# L506_M_V1_1.net
KiCad netlist of a schematic drawn in Altium Designer
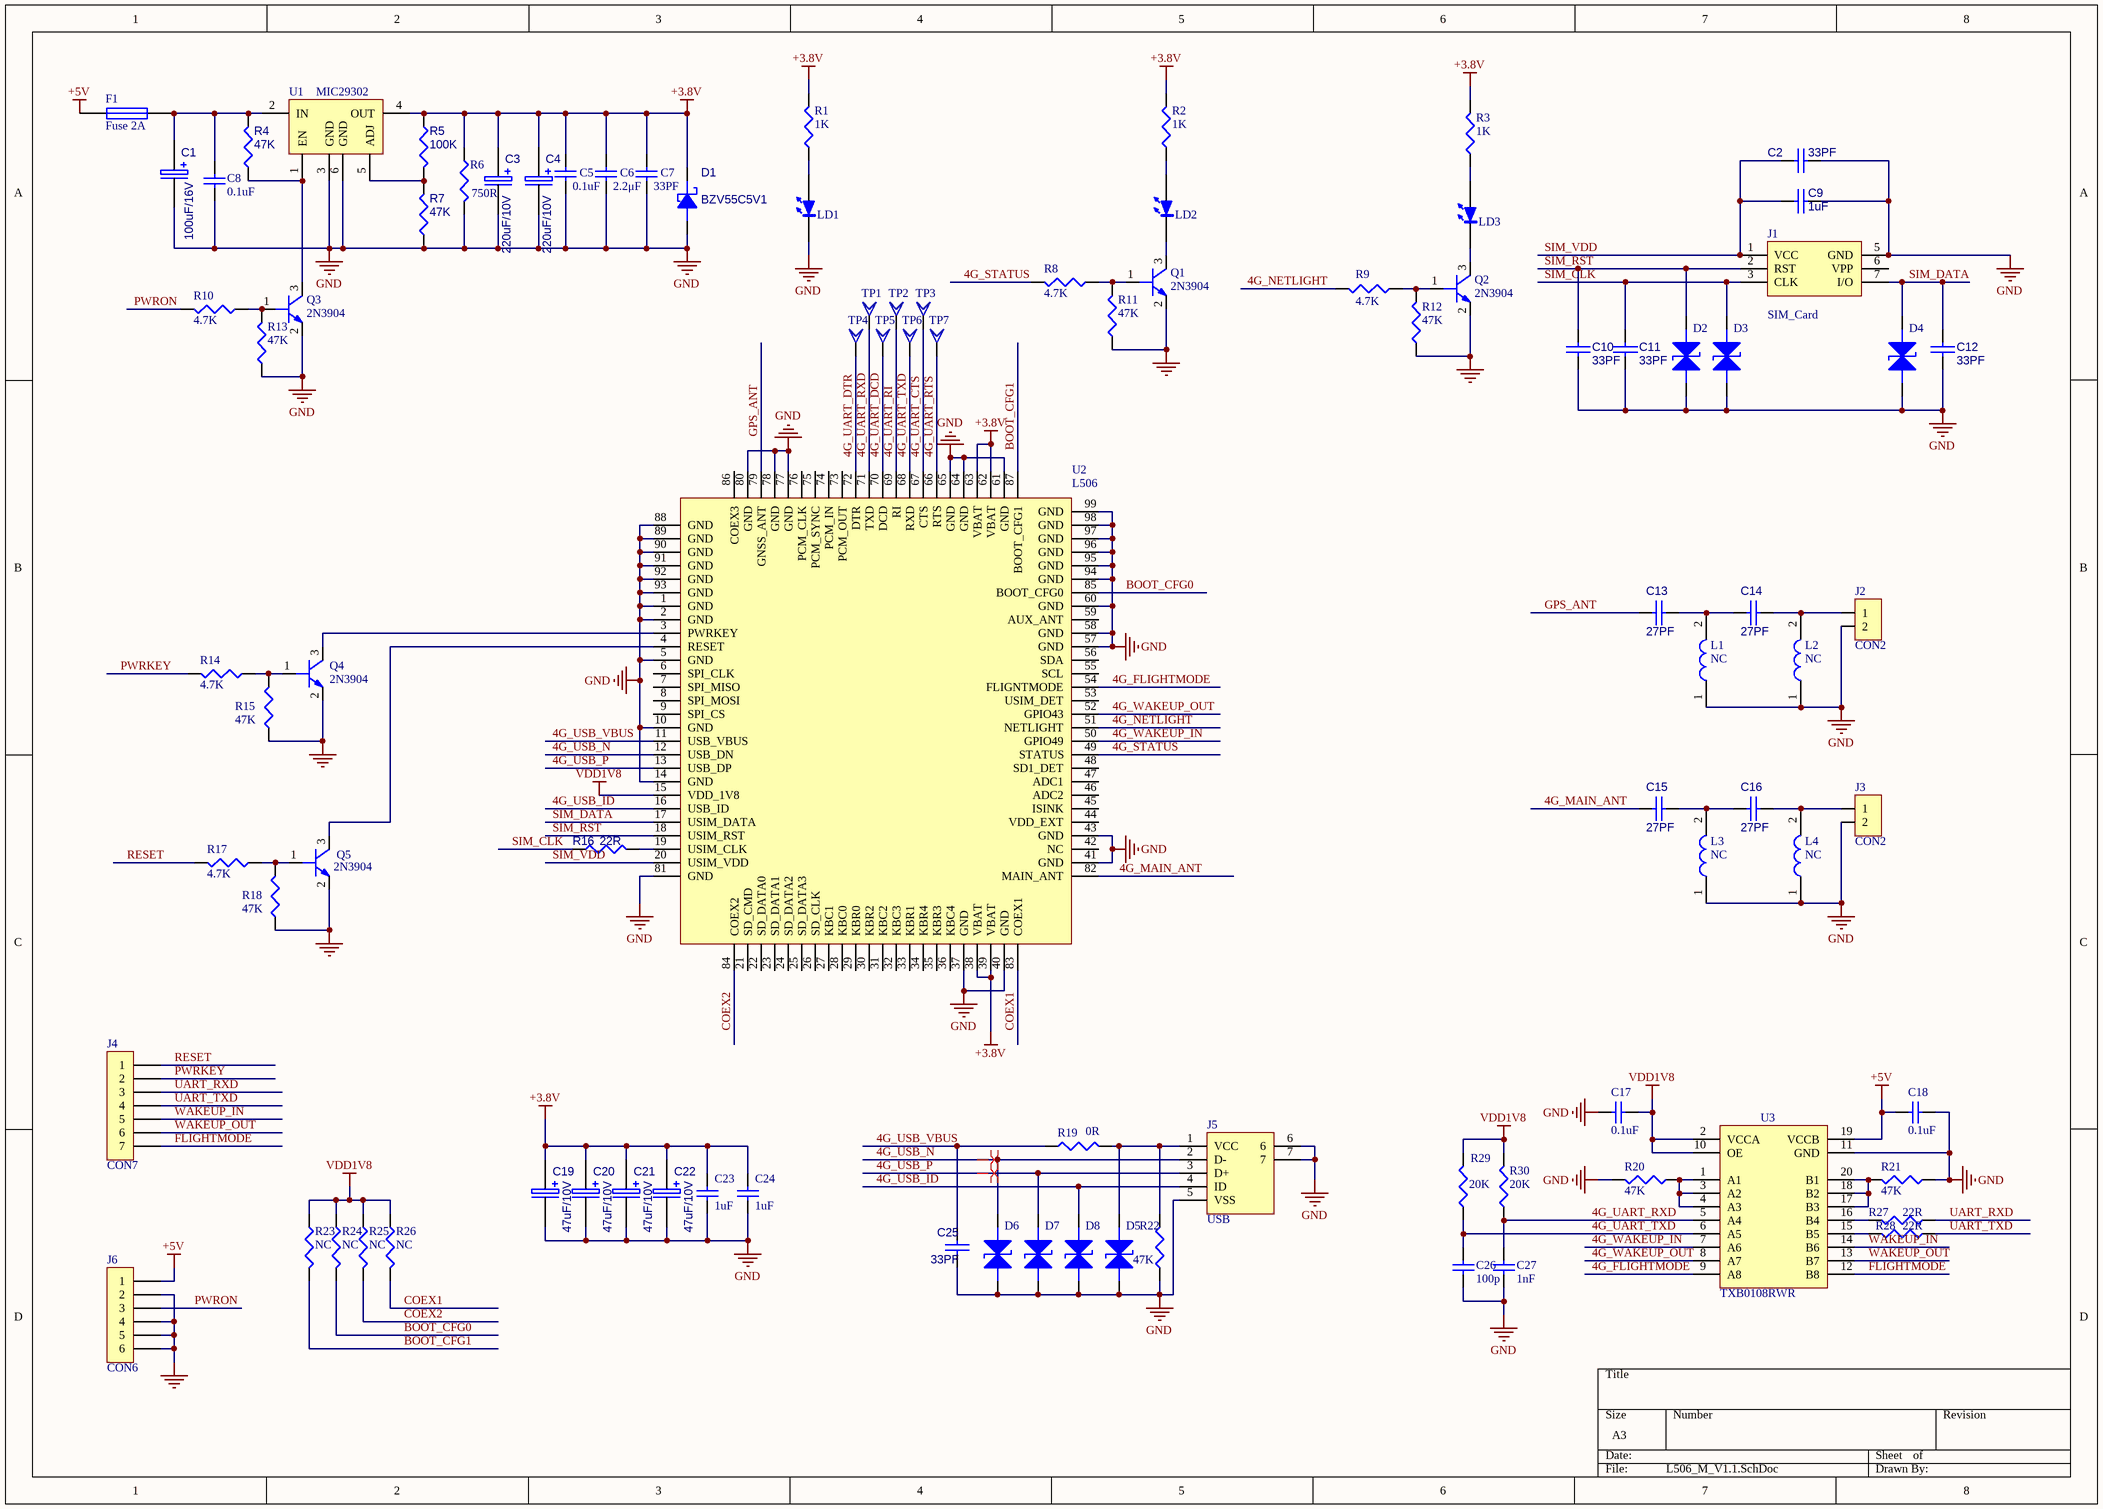
[diagram p0: L506_M_V1.1.SchDoc]

(export (version "E")
  (design (tool "Eeschema 10.0.6"))
  (components
    (comp (ref "C1")
      (value "100uF/16V")
      (footprint "C_TAN_C")
      (description "E-CAP")
      (libsource (lib "*") (part "ECAP"))
    )
    (comp (ref "C2")
      (value "33PF")
      (footprint "0603_C")
      (description "CAP")
      (libsource (lib "") (part "CAP_1"))
    )
    (comp (ref "C3")
      (value "220uF/10V")
      (footprint "C_TAN_D")
      (description "E-CAP")
      (libsource (lib "*") (part "ECAP"))
    )
    (comp (ref "C4")
      (value "220uF/10V")
      (footprint "C_TAN_D")
      (description "E-CAP")
      (libsource (lib "*") (part "ECAP"))
    )
    (comp (ref "C5")
      (value "0.1uF")
      (footprint "0603_C")
      (description "Capacitor")
      (fields (field (name "PUBLISHER") "Altium Limited"))
      (libsource (lib "EP_MCB_V3.00") (part "Cap Semi"))
    )
    (comp (ref "C6")
      (value "2.2μF")
      (footprint "0603_C")
      (description "Capacitor")
      (fields (field (name "PUBLISHER") "Altium Limited"))
      (libsource (lib "EP_MCB_V3.00") (part "Cap Semi"))
    )
    (comp (ref "C7")
      (value "33PF")
      (footprint "0603_C")
      (description "Capacitor")
      (fields (field (name "PUBLISHER") "Altium Limited"))
      (libsource (lib "EP_MCB_V3.00") (part "Cap Semi"))
    )
    (comp (ref "C8")
      (value "0.1uF")
      (footprint "0603_C")
      (description "Capacitor")
      (fields (field (name "PUBLISHER") "Altium Limited"))
      (libsource (lib "EP_MCB_V3.00") (part "Cap Semi"))
    )
    (comp (ref "C9")
      (value "1uF")
      (footprint "0603_C")
      (description "CAP")
      (libsource (lib "") (part "CAP_1"))
    )
    (comp (ref "C10")
      (value "33PF")
      (footprint "0603_C")
      (description "CAP")
      (libsource (lib "*") (part "CAP"))
    )
    (comp (ref "C11")
      (value "33PF")
      (footprint "0603_C")
      (description "CAP")
      (libsource (lib "*") (part "CAP"))
    )
    (comp (ref "C12")
      (value "33PF")
      (footprint "0603_C")
      (description "CAP")
      (libsource (lib "*") (part "CAP"))
    )
    (comp (ref "C13")
      (value "27PF")
      (footprint "0603_C")
      (description "CAP")
      (libsource (lib "") (part "CAP_1"))
    )
    (comp (ref "C14")
      (value "27PF")
      (footprint "0603_C")
      (description "CAP")
      (libsource (lib "") (part "CAP_1"))
    )
    (comp (ref "C15")
      (value "27PF")
      (footprint "0603_C")
      (description "CAP")
      (libsource (lib "") (part "CAP_1"))
    )
    (comp (ref "C16")
      (value "27PF")
      (footprint "0603_C")
      (description "CAP")
      (libsource (lib "") (part "CAP_1"))
    )
    (comp (ref "C17")
      (value "0.1uF")
      (footprint "0603_C")
      (description "Capacitor")
      (fields (field (name "PUBLISHER") "Altium Limited"))
      (libsource (lib "EP_MCB_V3.00") (part "Cap Semi"))
    )
    (comp (ref "C18")
      (value "0.1uF")
      (footprint "0603_C")
      (description "Capacitor")
      (fields (field (name "PUBLISHER") "Altium Limited"))
      (libsource (lib "EP_MCB_V3.00") (part "Cap Semi"))
    )
    (comp (ref "C19")
      (value "47uF/10V")
      (footprint "C_TAN_B")
      (description "E-CAP")
      (libsource (lib "*") (part "ECAP"))
    )
    (comp (ref "C20")
      (value "47uF/10V")
      (footprint "C_TAN_B")
      (description "E-CAP")
      (libsource (lib "*") (part "ECAP"))
    )
    (comp (ref "C21")
      (value "47uF/10V")
      (footprint "C_TAN_B")
      (description "E-CAP")
      (libsource (lib "*") (part "ECAP"))
    )
    (comp (ref "C22")
      (value "47uF/10V")
      (footprint "C_TAN_B")
      (description "E-CAP")
      (libsource (lib "*") (part "ECAP"))
    )
    (comp (ref "C23")
      (value "1uF")
      (footprint "0603_C")
      (description "Capacitor")
      (fields (field (name "PUBLISHER") "Altium Limited"))
      (libsource (lib "EP_MCB_V3.00") (part "Cap Semi"))
    )
    (comp (ref "C24")
      (value "1uF")
      (footprint "0603_C")
      (description "Capacitor")
      (fields (field (name "PUBLISHER") "Altium Limited"))
      (libsource (lib "EP_MCB_V3.00") (part "Cap Semi"))
    )
    (comp (ref "C25")
      (value "33PF")
      (footprint "0603_C")
      (description "CAP")
      (libsource (lib "*") (part "CAP"))
    )
    (comp (ref "C26")
      (value "100p")
      (footprint "0603_C")
      (description "Capacitor")
      (fields (field (name "PUBLISHER") "Altium Limited"))
      (libsource (lib "EP_MCB_V3.00") (part "Cap Semi"))
    )
    (comp (ref "C27")
      (value "1nF")
      (footprint "0603_C")
      (description "Capacitor")
      (fields (field (name "PUBLISHER") "Altium Limited"))
      (libsource (lib "EP_MCB_V3.00") (part "Cap Semi"))
    )
    (comp (ref "D1")
      (value "BZV55C5V1")
      (footprint "SOD-80")
      (libsource (lib "EP_MCB_V4.1") (part "DIODE SCHOTTKY"))
    )
    (comp (ref "D2")
      (value "EGA10603V05A1-B")
      (footprint "0603_R")
      (libsource (lib "MySchlib") (part "DIODE TVS BI-DIR"))
    )
    (comp (ref "D3")
      (value "EGA10603V05A1-B")
      (footprint "0603_R")
      (libsource (lib "MySchlib") (part "DIODE TVS BI-DIR"))
    )
    (comp (ref "D4")
      (value "EGA10603V05A1-B")
      (footprint "0603_R")
      (libsource (lib "MySchlib") (part "DIODE TVS BI-DIR"))
    )
    (comp (ref "D5")
      (value "EGA10603V05A1-B")
      (footprint "0603_R")
      (libsource (lib "MySchlib") (part "DIODE TVS BI-DIR"))
    )
    (comp (ref "D6")
      (value "EGA10603V05A1-B")
      (footprint "0603_R")
      (libsource (lib "MySchlib") (part "DIODE TVS BI-DIR"))
    )
    (comp (ref "D7")
      (value "EGA10603V05A1-B")
      (footprint "0603_R")
      (libsource (lib "MySchlib") (part "DIODE TVS BI-DIR"))
    )
    (comp (ref "D8")
      (value "EGA10603V05A1-B")
      (footprint "0603_R")
      (libsource (lib "MySchlib") (part "DIODE TVS BI-DIR"))
    )
    (comp (ref "F1")
      (value "Fuse 2A")
      (footprint "1812_F")
      (description "Fuse")
      (fields (field (name "PUBLISHER") "Altium Limited"))
      (libsource (lib "Miscellaneous Devices") (part "Fuse 1"))
    )
    (comp (ref "J1")
      (value "SIM_Card")
      (footprint "MicroSIM-6")
      (libsource (lib "MySchlib") (part "SIM_Card"))
    )
    (comp (ref "J2") (value "CON2") (footprint "RF-Z") (libsource (lib "MySchlib") (part "CON2")))
    (comp (ref "J3") (value "CON2") (footprint "RF-Z") (libsource (lib "MySchlib") (part "CON2")))
    (comp (ref "J4") (value "CON7") (footprint "SIP7") (libsource (lib "MySchlib") (part "CON7")))
    (comp (ref "J5") (value "USB") (libsource (lib "MySchlib") (part "USB-M")))
    (comp (ref "J6") (value "CON6") (footprint "SIP6") (libsource (lib "MySchlib") (part "CON6")))
    (comp (ref "L1") (value "NC") (footprint "0603_R") (libsource (lib "MySchlib") (part "L")))
    (comp (ref "L2") (value "NC") (footprint "0603_R") (libsource (lib "MySchlib") (part "L")))
    (comp (ref "L3") (value "NC") (footprint "0603_R") (libsource (lib "MySchlib") (part "L")))
    (comp (ref "L4") (value "NC") (footprint "0603_R") (libsource (lib "MySchlib") (part "L")))
    (comp (ref "LD1")
      (value "WHITE")
      (footprint "LED_0603")
      (description "LED")
      (libsource (lib "*") (part "LED"))
    )
    (comp (ref "LD2")
      (value "WHITE")
      (footprint "LED_0603")
      (description "LED")
      (libsource (lib "*") (part "LED"))
    )
    (comp (ref "LD3")
      (value "WHITE")
      (footprint "LED_0603")
      (description "LED")
      (libsource (lib "*") (part "LED"))
    )
    (comp (ref "Q1") (value "2N3904") (footprint "SOT23") (libsource (lib "MySchlib") (part "NPN")))
    (comp (ref "Q2") (value "2N3904") (footprint "SOT23") (libsource (lib "MySchlib") (part "NPN")))
    (comp (ref "Q3") (value "2N3904") (footprint "SOT23") (libsource (lib "MySchlib") (part "NPN")))
    (comp (ref "Q4") (value "2N3904") (footprint "SOT23") (libsource (lib "MySchlib") (part "NPN")))
    (comp (ref "Q5") (value "2N3904") (footprint "SOT23") (libsource (lib "MySchlib") (part "NPN")))
    (comp (ref "R1") (value "1K") (footprint "0603_R") (libsource (lib "MySchlib") (part "RES1")))
    (comp (ref "R2") (value "1K") (footprint "0603_R") (libsource (lib "MySchlib") (part "RES1")))
    (comp (ref "R3") (value "1K") (footprint "0603_R") (libsource (lib "MySchlib") (part "RES1")))
    (comp (ref "R4")
      (value "47K")
      (footprint "0603_R")
      (description "RESISTOR")
      (libsource (lib "*") (part "R0.25W"))
    )
    (comp (ref "R5")
      (value "100K")
      (footprint "0603_R")
      (description "RESISTOR")
      (libsource (lib "*") (part "R0.25W"))
    )
    (comp (ref "R6") (value "750R") (footprint "0603_R") (libsource (lib "") (part "RES1_1")))
    (comp (ref "R7")
      (value "47K")
      (footprint "0603_R")
      (description "RESISTOR")
      (libsource (lib "*") (part "R0.25W"))
    )
    (comp (ref "R8") (value "4.7K") (footprint "0603_R") (libsource (lib "MySchlib") (part "RES1")))
    (comp (ref "R9") (value "4.7K") (footprint "0603_R") (libsource (lib "MySchlib") (part "RES1")))
    (comp (ref "R10") (value "4.7K") (footprint "0603_R") (libsource (lib "MySchlib") (part "RES1")))
    (comp (ref "R11") (value "47K") (footprint "0603_R") (libsource (lib "MySchlib") (part "RES1")))
    (comp (ref "R12") (value "47K") (footprint "0603_R") (libsource (lib "MySchlib") (part "RES1")))
    (comp (ref "R13") (value "47K") (footprint "0603_R") (libsource (lib "MySchlib") (part "RES1")))
    (comp (ref "R14") (value "4.7K") (footprint "0603_R") (libsource (lib "MySchlib") (part "RES1")))
    (comp (ref "R15") (value "47K") (footprint "0603_R") (libsource (lib "MySchlib") (part "RES1")))
    (comp (ref "R16")
      (value "22R")
      (footprint "0603_R")
      (description "RESISTOR")
      (libsource (lib "*") (part "R0.25W"))
    )
    (comp (ref "R17") (value "4.7K") (footprint "0603_R") (libsource (lib "MySchlib") (part "RES1")))
    (comp (ref "R18") (value "47K") (footprint "0603_R") (libsource (lib "MySchlib") (part "RES1")))
    (comp (ref "R19") (value "0R") (footprint "0603_R") (libsource (lib "MySchlib") (part "RES1")))
    (comp (ref "R20") (value "47K") (footprint "0603_R") (libsource (lib "MySchlib") (part "RES1")))
    (comp (ref "R21") (value "47K") (footprint "0603_R") (libsource (lib "MySchlib") (part "RES1")))
    (comp (ref "R22") (value "47K") (footprint "0603_R") (libsource (lib "MySchlib") (part "RES1")))
    (comp (ref "R23") (value "NC") (footprint "0603_R") (libsource (lib "MySchlib") (part "RES1")))
    (comp (ref "R24") (value "NC") (footprint "0603_R") (libsource (lib "MySchlib") (part "RES1")))
    (comp (ref "R25") (value "NC") (footprint "0603_R") (libsource (lib "MySchlib") (part "RES1")))
    (comp (ref "R26") (value "NC") (footprint "0603_R") (libsource (lib "MySchlib") (part "RES1")))
    (comp (ref "R27") (value "22R") (footprint "0603_R") (libsource (lib "MySchlib") (part "RES1")))
    (comp (ref "R28") (value "22R") (footprint "0603_R") (libsource (lib "MySchlib") (part "RES1")))
    (comp (ref "R29") (value "20K") (footprint "0603_R") (libsource (lib "MySchlib") (part "RES1")))
    (comp (ref "R30") (value "20K") (footprint "0603_R") (libsource (lib "MySchlib") (part "RES1")))
    (comp (ref "TP1")
      (value "Component_1")
      (footprint "TP-40")
      (libsource (lib "MySchlib") (part "Component_1"))
    )
    (comp (ref "TP2")
      (value "Component_1")
      (footprint "TP-40")
      (libsource (lib "MySchlib") (part "Component_1"))
    )
    (comp (ref "TP3")
      (value "Component_1")
      (footprint "TP-40")
      (libsource (lib "MySchlib") (part "Component_1"))
    )
    (comp (ref "TP4")
      (value "Component_1")
      (footprint "TP-40")
      (libsource (lib "MySchlib") (part "Component_1"))
    )
    (comp (ref "TP5")
      (value "Component_1")
      (footprint "TP-40")
      (libsource (lib "MySchlib") (part "Component_1"))
    )
    (comp (ref "TP6")
      (value "Component_1")
      (footprint "TP-40")
      (libsource (lib "MySchlib") (part "Component_1"))
    )
    (comp (ref "TP7")
      (value "Component_1")
      (footprint "TP-40")
      (libsource (lib "MySchlib") (part "Component_1"))
    )
    (comp (ref "U1") (value "MIC29302") (footprint "TO-263-5") (libsource (lib "MySchlib") (part "MIC29302")))
    (comp (ref "U2") (value "L506") (footprint "L506") (libsource (lib "MySchlib") (part "L506")))
    (comp (ref "U3")
      (value "TXB0108RWR")
      (footprint "TSSP20")
      (libsource (lib "MySchlib") (part "TXB0108RGYR"))
    )
  )
  (nets
    (net (code "1") (name "+3.8V") (class "Default")
      (node (ref "C19") (pin "1") (pinfunction "+_1") (pintype "passive"))
      (node (ref "C20") (pin "1") (pinfunction "+_1") (pintype "passive"))
      (node (ref "C21") (pin "1") (pinfunction "+_1") (pintype "passive"))
      (node (ref "C22") (pin "1") (pinfunction "+_1") (pintype "passive"))
      (node (ref "C23") (pin "2") (pinfunction "2_2") (pintype "passive"))
      (node (ref "C24") (pin "2") (pinfunction "2_2") (pintype "passive"))
      (node (ref "C3") (pin "1") (pinfunction "+_1") (pintype "passive"))
      (node (ref "C4") (pin "1") (pinfunction "+_1") (pintype "passive"))
      (node (ref "C5") (pin "2") (pinfunction "2_2") (pintype "passive"))
      (node (ref "C6") (pin "2") (pinfunction "2_2") (pintype "passive"))
      (node (ref "C7") (pin "2") (pinfunction "2_2") (pintype "passive"))
      (node (ref "D1") (pin "2") (pinfunction "CATHODE_2") (pintype "passive"))
      (node (ref "R1") (pin "1") (pinfunction "1_1") (pintype "passive"))
      (node (ref "R2") (pin "1") (pinfunction "1_1") (pintype "passive"))
      (node (ref "R3") (pin "1") (pinfunction "1_1") (pintype "passive"))
      (node (ref "R5") (pin "2") (pinfunction "2_2") (pintype "passive"))
      (node (ref "R6") (pin "2") (pinfunction "2_2") (pintype "passive"))
      (node (ref "U1") (pin "4") (pinfunction "OUT_4") (pintype "passive"))
      (node (ref "U2") (pin "38") (pinfunction "VBAT_38") (pintype "passive"))
      (node (ref "U2") (pin "39") (pinfunction "VBAT_39") (pintype "passive"))
      (node (ref "U2") (pin "62") (pinfunction "VBAT_62") (pintype "passive"))
      (node (ref "U2") (pin "63") (pinfunction "VBAT_63") (pintype "passive"))
    )
    (net (code "2") (name "+5V") (class "Default")
      (node (ref "C18") (pin "2") (pinfunction "2_2") (pintype "passive"))
      (node (ref "F1") (pin "1") (pinfunction "1_1") (pintype "passive"))
      (node (ref "J6") (pin "1") (pinfunction "1_1") (pintype "passive"))
      (node (ref "U3") (pin "19") (pinfunction "VCCB_19") (pintype "passive"))
    )
    (net (code "3") (name "/4G_FLIGHTMODE") (class "Default")
      (node (ref "U2") (pin "54") (pinfunction "FLIGNTMODE_54") (pintype "passive"))
      (node (ref "U3") (pin "9") (pinfunction "A8_9") (pintype "passive"))
    )
    (net (code "4") (name "/4G_MAIN_ANT") (class "Default")
      (node (ref "C15") (pin "1") (pinfunction "1_1") (pintype "passive"))
      (node (ref "U2") (pin "82") (pinfunction "MAIN_ANT_82") (pintype "passive"))
    )
    (net (code "5") (name "/4G_NETLIGHT") (class "Default")
      (node (ref "R9") (pin "1") (pinfunction "1_1") (pintype "passive"))
      (node (ref "U2") (pin "51") (pinfunction "NETLIGHT_51") (pintype "passive"))
    )
    (net (code "6") (name "/4G_STATUS") (class "Default")
      (node (ref "R8") (pin "1") (pinfunction "1_1") (pintype "passive"))
      (node (ref "U2") (pin "49") (pinfunction "STATUS_49") (pintype "passive"))
    )
    (net (code "7") (name "/4G_UART_CTS") (class "Default")
      (node (ref "TP3") (pin "1") (pinfunction "1_1") (pintype "passive"))
      (node (ref "U2") (pin "67") (pinfunction "CTS_67") (pintype "passive"))
    )
    (net (code "8") (name "/4G_UART_DCD") (class "Default")
      (node (ref "TP5") (pin "1") (pinfunction "1_1") (pintype "passive"))
      (node (ref "U2") (pin "70") (pinfunction "DCD_70") (pintype "passive"))
    )
    (net (code "9") (name "/4G_UART_DTR") (class "Default")
      (node (ref "TP4") (pin "1") (pinfunction "1_1") (pintype "passive"))
      (node (ref "U2") (pin "72") (pinfunction "DTR_72") (pintype "passive"))
    )
    (net (code "10") (name "/4G_UART_RI") (class "Default")
      (node (ref "TP2") (pin "1") (pinfunction "1_1") (pintype "passive"))
      (node (ref "U2") (pin "69") (pinfunction "RI_69") (pintype "passive"))
    )
    (net (code "11") (name "/4G_UART_RTS") (class "Default")
      (node (ref "TP7") (pin "1") (pinfunction "1_1") (pintype "passive"))
      (node (ref "U2") (pin "66") (pinfunction "RTS_66") (pintype "passive"))
    )
    (net (code "12") (name "/4G_UART_RXD") (class "Default")
      (node (ref "C27") (pin "2") (pinfunction "2_2") (pintype "passive"))
      (node (ref "R30") (pin "1") (pinfunction "1_1") (pintype "passive"))
      (node (ref "TP1") (pin "1") (pinfunction "1_1") (pintype "passive"))
      (node (ref "U2") (pin "71") (pinfunction "TXD_71") (pintype "passive"))
      (node (ref "U3") (pin "5") (pinfunction "A4_5") (pintype "passive"))
    )
    (net (code "13") (name "/4G_UART_TXD") (class "Default")
      (node (ref "C26") (pin "2") (pinfunction "2_2") (pintype "passive"))
      (node (ref "R29") (pin "1") (pinfunction "1_1") (pintype "passive"))
      (node (ref "TP6") (pin "1") (pinfunction "1_1") (pintype "passive"))
      (node (ref "U2") (pin "68") (pinfunction "RXD_68") (pintype "passive"))
      (node (ref "U3") (pin "6") (pinfunction "A5_6") (pintype "passive"))
    )
    (net (code "14") (name "/4G_USB_ID") (class "Default")
      (node (ref "D8") (pin "2") (pinfunction "2_2") (pintype "passive"))
      (node (ref "J5") (pin "4") (pinfunction "ID_4") (pintype "passive"))
      (node (ref "U2") (pin "16") (pinfunction "USB_ID_16") (pintype "passive"))
    )
    (net (code "15") (name "/4G_USB_N") (class "Default")
      (node (ref "D6") (pin "2") (pinfunction "2_2") (pintype "passive"))
      (node (ref "J5") (pin "2") (pinfunction "D-_2") (pintype "passive"))
      (node (ref "U2") (pin "12") (pinfunction "USB_DN_12") (pintype "passive"))
    )
    (net (code "16") (name "/4G_USB_P") (class "Default")
      (node (ref "D7") (pin "2") (pinfunction "2_2") (pintype "passive"))
      (node (ref "J5") (pin "3") (pinfunction "D+_3") (pintype "passive"))
      (node (ref "U2") (pin "13") (pinfunction "USB_DP_13") (pintype "passive"))
    )
    (net (code "17") (name "/4G_USB_VBUS") (class "Default")
      (node (ref "C25") (pin "2") (pinfunction "2_2") (pintype "passive"))
      (node (ref "R19") (pin "1") (pinfunction "1_1") (pintype "passive"))
      (node (ref "U2") (pin "11") (pinfunction "USB_VBUS_11") (pintype "passive"))
    )
    (net (code "18") (name "/4G_WAKEUP_IN") (class "Default")
      (node (ref "U2") (pin "50") (pinfunction "GPIO49_50") (pintype "passive"))
      (node (ref "U3") (pin "7") (pinfunction "A6_7") (pintype "passive"))
    )
    (net (code "19") (name "/4G_WAKEUP_OUT") (class "Default")
      (node (ref "U2") (pin "52") (pinfunction "GPIO43_52") (pintype "passive"))
      (node (ref "U3") (pin "8") (pinfunction "A7_8") (pintype "passive"))
    )
    (net (code "20") (name "/BOOT_CFG0") (class "Default")
      (node (ref "R24") (pin "2") (pinfunction "2_2") (pintype "passive"))
      (node (ref "U2") (pin "85") (pinfunction "BOOT_CFG0_85") (pintype "passive"))
    )
    (net (code "21") (name "/BOOT_CFG1") (class "Default")
      (node (ref "R23") (pin "2") (pinfunction "2_2") (pintype "passive"))
      (node (ref "U2") (pin "87") (pinfunction "BOOT_CFG1_87") (pintype "passive"))
    )
    (net (code "22") (name "/COEX1") (class "Default")
      (node (ref "R26") (pin "2") (pinfunction "2_2") (pintype "passive"))
      (node (ref "U2") (pin "83") (pinfunction "COEX1_83") (pintype "passive"))
    )
    (net (code "23") (name "/COEX2") (class "Default")
      (node (ref "R25") (pin "2") (pinfunction "2_2") (pintype "passive"))
      (node (ref "U2") (pin "84") (pinfunction "COEX2_84") (pintype "passive"))
    )
    (net (code "24") (name "/FLIGHTMODE") (class "Default")
      (node (ref "J4") (pin "7") (pinfunction "7_7") (pintype "passive"))
      (node (ref "U3") (pin "12") (pinfunction "B8_12") (pintype "passive"))
    )
    (net (code "25") (name "/GPS_ANT") (class "Default")
      (node (ref "C13") (pin "1") (pinfunction "1_1") (pintype "passive"))
      (node (ref "U2") (pin "79") (pinfunction "GNSS_ANT_79") (pintype "passive"))
    )
    (net (code "26") (name "/PWRKEY") (class "Default")
      (node (ref "J4") (pin "2") (pinfunction "2_2") (pintype "passive"))
      (node (ref "R14") (pin "1") (pinfunction "1_1") (pintype "passive"))
    )
    (net (code "27") (name "/PWRON") (class "Default")
      (node (ref "J6") (pin "3") (pinfunction "3_3") (pintype "passive"))
      (node (ref "R10") (pin "1") (pinfunction "1_1") (pintype "passive"))
    )
    (net (code "28") (name "/RESET") (class "Default")
      (node (ref "J4") (pin "1") (pinfunction "1_1") (pintype "passive"))
      (node (ref "R17") (pin "1") (pinfunction "1_1") (pintype "passive"))
    )
    (net (code "29") (name "/SIM_CLK") (class "Default")
      (node (ref "C11") (pin "2") (pinfunction "2_2") (pintype "passive"))
      (node (ref "D3") (pin "2") (pinfunction "2_2") (pintype "passive"))
      (node (ref "J1") (pin "3") (pinfunction "CLK_3") (pintype "passive"))
      (node (ref "R16") (pin "1") (pinfunction "1_1") (pintype "passive"))
    )
    (net (code "30") (name "/SIM_DATA") (class "Default")
      (node (ref "C12") (pin "2") (pinfunction "2_2") (pintype "passive"))
      (node (ref "D4") (pin "2") (pinfunction "2_2") (pintype "passive"))
      (node (ref "J1") (pin "7") (pinfunction "I/O_7") (pintype "passive"))
      (node (ref "U2") (pin "17") (pinfunction "USIM_DATA_17") (pintype "passive"))
    )
    (net (code "31") (name "/SIM_RST") (class "Default")
      (node (ref "C10") (pin "2") (pinfunction "2_2") (pintype "passive"))
      (node (ref "D2") (pin "2") (pinfunction "2_2") (pintype "passive"))
      (node (ref "J1") (pin "2") (pinfunction "RST_2") (pintype "passive"))
      (node (ref "U2") (pin "18") (pinfunction "USIM_RST_18") (pintype "passive"))
    )
    (net (code "32") (name "/SIM_VDD") (class "Default")
      (node (ref "C2") (pin "1") (pinfunction "1_1") (pintype "passive"))
      (node (ref "C9") (pin "1") (pinfunction "1_1") (pintype "passive"))
      (node (ref "J1") (pin "1") (pinfunction "VCC_1") (pintype "passive"))
      (node (ref "U2") (pin "20") (pinfunction "USIM_VDD_20") (pintype "passive"))
    )
    (net (code "33") (name "/UART_RXD") (class "Default")
      (node (ref "J4") (pin "3") (pinfunction "3_3") (pintype "passive"))
      (node (ref "R27") (pin "1") (pinfunction "1_1") (pintype "passive"))
    )
    (net (code "34") (name "/UART_TXD") (class "Default")
      (node (ref "J4") (pin "4") (pinfunction "4_4") (pintype "passive"))
      (node (ref "R28") (pin "1") (pinfunction "1_1") (pintype "passive"))
    )
    (net (code "35") (name "/WAKEUP_IN") (class "Default")
      (node (ref "J4") (pin "5") (pinfunction "5_5") (pintype "passive"))
      (node (ref "U3") (pin "14") (pinfunction "B6_14") (pintype "passive"))
    )
    (net (code "36") (name "/WAKEUP_OUT") (class "Default")
      (node (ref "J4") (pin "6") (pinfunction "6_6") (pintype "passive"))
      (node (ref "U3") (pin "13") (pinfunction "B7_13") (pintype "passive"))
    )
    (net (code "37") (name "GND") (class "Default")
      (node (ref "C1") (pin "2") (pinfunction "-_2") (pintype "passive"))
      (node (ref "C10") (pin "1") (pinfunction "1_1") (pintype "passive"))
      (node (ref "C11") (pin "1") (pinfunction "1_1") (pintype "passive"))
      (node (ref "C12") (pin "1") (pinfunction "1_1") (pintype "passive"))
      (node (ref "C17") (pin "1") (pinfunction "1_1") (pintype "passive"))
      (node (ref "C18") (pin "1") (pinfunction "1_1") (pintype "passive"))
      (node (ref "C19") (pin "2") (pinfunction "-_2") (pintype "passive"))
      (node (ref "C2") (pin "2") (pinfunction "2_2") (pintype "passive"))
      (node (ref "C20") (pin "2") (pinfunction "-_2") (pintype "passive"))
      (node (ref "C21") (pin "2") (pinfunction "-_2") (pintype "passive"))
      (node (ref "C22") (pin "2") (pinfunction "-_2") (pintype "passive"))
      (node (ref "C23") (pin "1") (pinfunction "1_1") (pintype "passive"))
      (node (ref "C24") (pin "1") (pinfunction "1_1") (pintype "passive"))
      (node (ref "C25") (pin "1") (pinfunction "1_1") (pintype "passive"))
      (node (ref "C26") (pin "1") (pinfunction "1_1") (pintype "passive"))
      (node (ref "C27") (pin "1") (pinfunction "1_1") (pintype "passive"))
      (node (ref "C3") (pin "2") (pinfunction "-_2") (pintype "passive"))
      (node (ref "C4") (pin "2") (pinfunction "-_2") (pintype "passive"))
      (node (ref "C5") (pin "1") (pinfunction "1_1") (pintype "passive"))
      (node (ref "C6") (pin "1") (pinfunction "1_1") (pintype "passive"))
      (node (ref "C7") (pin "1") (pinfunction "1_1") (pintype "passive"))
      (node (ref "C8") (pin "1") (pinfunction "1_1") (pintype "passive"))
      (node (ref "C9") (pin "2") (pinfunction "2_2") (pintype "passive"))
      (node (ref "D1") (pin "1") (pinfunction "ANODE_1") (pintype "passive"))
      (node (ref "D2") (pin "1") (pinfunction "1_1") (pintype "passive"))
      (node (ref "D3") (pin "1") (pinfunction "1_1") (pintype "passive"))
      (node (ref "D4") (pin "1") (pinfunction "1_1") (pintype "passive"))
      (node (ref "D5") (pin "1") (pinfunction "1_1") (pintype "passive"))
      (node (ref "D6") (pin "1") (pinfunction "1_1") (pintype "passive"))
      (node (ref "D7") (pin "1") (pinfunction "1_1") (pintype "passive"))
      (node (ref "D8") (pin "1") (pinfunction "1_1") (pintype "passive"))
      (node (ref "J1") (pin "5") (pinfunction "GND_5") (pintype "passive"))
      (node (ref "J2") (pin "2") (pinfunction "2_2") (pintype "passive"))
      (node (ref "J3") (pin "2") (pinfunction "2_2") (pintype "passive"))
      (node (ref "J5") (pin "5") (pinfunction "VSS_5") (pintype "passive"))
      (node (ref "J5") (pin "6") (pinfunction "6_6") (pintype "passive"))
      (node (ref "J5") (pin "7") (pinfunction "7_7") (pintype "passive"))
      (node (ref "J6") (pin "2") (pinfunction "2_2") (pintype "passive"))
      (node (ref "J6") (pin "4") (pinfunction "4_4") (pintype "passive"))
      (node (ref "J6") (pin "5") (pinfunction "5_5") (pintype "passive"))
      (node (ref "J6") (pin "6") (pinfunction "6_6") (pintype "passive"))
      (node (ref "L1") (pin "1") (pinfunction "1_1") (pintype "passive"))
      (node (ref "L2") (pin "1") (pinfunction "1_1") (pintype "passive"))
      (node (ref "L3") (pin "1") (pinfunction "1_1") (pintype "passive"))
      (node (ref "L4") (pin "1") (pinfunction "1_1") (pintype "passive"))
      (node (ref "LD1") (pin "K") (pinfunction "K_K") (pintype "passive"))
      (node (ref "Q1") (pin "2") (pinfunction "EMITTER_2") (pintype "passive"))
      (node (ref "Q2") (pin "2") (pinfunction "EMITTER_2") (pintype "passive"))
      (node (ref "Q3") (pin "2") (pinfunction "EMITTER_2") (pintype "passive"))
      (node (ref "Q4") (pin "2") (pinfunction "EMITTER_2") (pintype "passive"))
      (node (ref "Q5") (pin "2") (pinfunction "EMITTER_2") (pintype "passive"))
      (node (ref "R11") (pin "2") (pinfunction "2_2") (pintype "passive"))
      (node (ref "R12") (pin "2") (pinfunction "2_2") (pintype "passive"))
      (node (ref "R13") (pin "2") (pinfunction "2_2") (pintype "passive"))
      (node (ref "R15") (pin "2") (pinfunction "2_2") (pintype "passive"))
      (node (ref "R18") (pin "2") (pinfunction "2_2") (pintype "passive"))
      (node (ref "R20") (pin "2") (pinfunction "2_2") (pintype "passive"))
      (node (ref "R21") (pin "1") (pinfunction "1_1") (pintype "passive"))
      (node (ref "R22") (pin "2") (pinfunction "2_2") (pintype "passive"))
      (node (ref "R6") (pin "1") (pinfunction "1_1") (pintype "passive"))
      (node (ref "R7") (pin "2") (pinfunction "2_2") (pintype "passive"))
      (node (ref "U1") (pin "3") (pinfunction "GND_3") (pintype "passive"))
      (node (ref "U1") (pin "6") (pinfunction "GND_6") (pintype "passive"))
      (node (ref "U2") (pin "1") (pinfunction "GND_1") (pintype "passive"))
      (node (ref "U2") (pin "10") (pinfunction "GND_10") (pintype "passive"))
      (node (ref "U2") (pin "14") (pinfunction "GND_14") (pintype "passive"))
      (node (ref "U2") (pin "2") (pinfunction "GND_2") (pintype "passive"))
      (node (ref "U2") (pin "37") (pinfunction "GND_37") (pintype "passive"))
      (node (ref "U2") (pin "40") (pinfunction "GND_40") (pintype "passive"))
      (node (ref "U2") (pin "41") (pinfunction "GND_41") (pintype "passive"))
      (node (ref "U2") (pin "43") (pinfunction "GND_43") (pintype "passive"))
      (node (ref "U2") (pin "5") (pinfunction "GND_5") (pintype "passive"))
      (node (ref "U2") (pin "57") (pinfunction "GND_57") (pintype "passive"))
      (node (ref "U2") (pin "58") (pinfunction "GND_58") (pintype "passive"))
      (node (ref "U2") (pin "60") (pinfunction "GND_60") (pintype "passive"))
      (node (ref "U2") (pin "61") (pinfunction "GND_61") (pintype "passive"))
      (node (ref "U2") (pin "64") (pinfunction "GND_64") (pintype "passive"))
      (node (ref "U2") (pin "65") (pinfunction "GND_65") (pintype "passive"))
      (node (ref "U2") (pin "77") (pinfunction "GND_77") (pintype "passive"))
      (node (ref "U2") (pin "78") (pinfunction "GND_78") (pintype "passive"))
      (node (ref "U2") (pin "80") (pinfunction "GND_80") (pintype "passive"))
      (node (ref "U2") (pin "81") (pinfunction "GND_81") (pintype "passive"))
      (node (ref "U2") (pin "88") (pinfunction "GND_88") (pintype "passive"))
      (node (ref "U2") (pin "89") (pinfunction "GND_89") (pintype "passive"))
      (node (ref "U2") (pin "90") (pinfunction "GND_90") (pintype "passive"))
      (node (ref "U2") (pin "91") (pinfunction "GND_91") (pintype "passive"))
      (node (ref "U2") (pin "92") (pinfunction "GND_92") (pintype "passive"))
      (node (ref "U2") (pin "93") (pinfunction "GND_93") (pintype "passive"))
      (node (ref "U2") (pin "94") (pinfunction "GND_94") (pintype "passive"))
      (node (ref "U2") (pin "95") (pinfunction "GND_95") (pintype "passive"))
      (node (ref "U2") (pin "96") (pinfunction "GND_96") (pintype "passive"))
      (node (ref "U2") (pin "97") (pinfunction "GND_97") (pintype "passive"))
      (node (ref "U2") (pin "98") (pinfunction "GND_98") (pintype "passive"))
      (node (ref "U2") (pin "99") (pinfunction "GND_99") (pintype "passive"))
      (node (ref "U3") (pin "11") (pinfunction "GND_11") (pintype "passive"))
    )
    (net (code "38") (name "Net-(C1-+)") (class "Default")
      (node (ref "C1") (pin "1") (pinfunction "+_1") (pintype "passive"))
      (node (ref "C8") (pin "2") (pinfunction "2_2") (pintype "passive"))
      (node (ref "F1") (pin "2") (pinfunction "2_2") (pintype "passive"))
      (node (ref "R4") (pin "1") (pinfunction "1_1") (pintype "passive"))
      (node (ref "U1") (pin "2") (pinfunction "IN_2") (pintype "passive"))
    )
    (net (code "39") (name "Net-(C13-Pad2)") (class "Default")
      (node (ref "C13") (pin "2") (pinfunction "2_2") (pintype "passive"))
      (node (ref "C14") (pin "1") (pinfunction "1_1") (pintype "passive"))
      (node (ref "L1") (pin "2") (pinfunction "2_2") (pintype "passive"))
    )
    (net (code "40") (name "Net-(C14-Pad2)") (class "Default")
      (node (ref "C14") (pin "2") (pinfunction "2_2") (pintype "passive"))
      (node (ref "J2") (pin "1") (pinfunction "1_1") (pintype "passive"))
      (node (ref "L2") (pin "2") (pinfunction "2_2") (pintype "passive"))
    )
    (net (code "41") (name "Net-(C15-Pad2)") (class "Default")
      (node (ref "C15") (pin "2") (pinfunction "2_2") (pintype "passive"))
      (node (ref "C16") (pin "1") (pinfunction "1_1") (pintype "passive"))
      (node (ref "L3") (pin "2") (pinfunction "2_2") (pintype "passive"))
    )
    (net (code "42") (name "Net-(C16-Pad2)") (class "Default")
      (node (ref "C16") (pin "2") (pinfunction "2_2") (pintype "passive"))
      (node (ref "J3") (pin "1") (pinfunction "1_1") (pintype "passive"))
      (node (ref "L4") (pin "2") (pinfunction "2_2") (pintype "passive"))
    )
    (net (code "43") (name "Net-(J5-VCC)") (class "Default")
      (node (ref "D5") (pin "2") (pinfunction "2_2") (pintype "passive"))
      (node (ref "J5") (pin "1") (pinfunction "VCC_1") (pintype "passive"))
      (node (ref "R19") (pin "2") (pinfunction "2_2") (pintype "passive"))
      (node (ref "R22") (pin "1") (pinfunction "1_1") (pintype "passive"))
    )
    (net (code "44") (name "Net-(LD1-PadA)") (class "Default")
      (node (ref "LD1") (pin "A") (pinfunction "A_A") (pintype "passive"))
      (node (ref "R1") (pin "2") (pinfunction "2_2") (pintype "passive"))
    )
    (net (code "45") (name "Net-(LD2-PadA)") (class "Default")
      (node (ref "LD2") (pin "A") (pinfunction "A_A") (pintype "passive"))
      (node (ref "R2") (pin "2") (pinfunction "2_2") (pintype "passive"))
    )
    (net (code "46") (name "Net-(LD3-PadA)") (class "Default")
      (node (ref "LD3") (pin "A") (pinfunction "A_A") (pintype "passive"))
      (node (ref "R3") (pin "2") (pinfunction "2_2") (pintype "passive"))
    )
    (net (code "47") (name "Net-(Q1-BASE)") (class "Default")
      (node (ref "Q1") (pin "1") (pinfunction "BASE_1") (pintype "passive"))
      (node (ref "R11") (pin "1") (pinfunction "1_1") (pintype "passive"))
      (node (ref "R8") (pin "2") (pinfunction "2_2") (pintype "passive"))
    )
    (net (code "48") (name "Net-(Q1-COLLECTOR)") (class "Default")
      (node (ref "LD2") (pin "K") (pinfunction "K_K") (pintype "passive"))
      (node (ref "Q1") (pin "3") (pinfunction "COLLECTOR_3") (pintype "passive"))
    )
    (net (code "49") (name "Net-(Q2-BASE)") (class "Default")
      (node (ref "Q2") (pin "1") (pinfunction "BASE_1") (pintype "passive"))
      (node (ref "R12") (pin "1") (pinfunction "1_1") (pintype "passive"))
      (node (ref "R9") (pin "2") (pinfunction "2_2") (pintype "passive"))
    )
    (net (code "50") (name "Net-(Q2-COLLECTOR)") (class "Default")
      (node (ref "LD3") (pin "K") (pinfunction "K_K") (pintype "passive"))
      (node (ref "Q2") (pin "3") (pinfunction "COLLECTOR_3") (pintype "passive"))
    )
    (net (code "51") (name "Net-(Q3-BASE)") (class "Default")
      (node (ref "Q3") (pin "1") (pinfunction "BASE_1") (pintype "passive"))
      (node (ref "R10") (pin "2") (pinfunction "2_2") (pintype "passive"))
      (node (ref "R13") (pin "1") (pinfunction "1_1") (pintype "passive"))
    )
    (net (code "52") (name "Net-(Q3-COLLECTOR)") (class "Default")
      (node (ref "Q3") (pin "3") (pinfunction "COLLECTOR_3") (pintype "passive"))
      (node (ref "R4") (pin "2") (pinfunction "2_2") (pintype "passive"))
      (node (ref "U1") (pin "1") (pinfunction "EN_1") (pintype "passive"))
    )
    (net (code "53") (name "Net-(Q4-BASE)") (class "Default")
      (node (ref "Q4") (pin "1") (pinfunction "BASE_1") (pintype "passive"))
      (node (ref "R14") (pin "2") (pinfunction "2_2") (pintype "passive"))
      (node (ref "R15") (pin "1") (pinfunction "1_1") (pintype "passive"))
    )
    (net (code "54") (name "Net-(Q4-COLLECTOR)") (class "Default")
      (node (ref "Q4") (pin "3") (pinfunction "COLLECTOR_3") (pintype "passive"))
      (node (ref "U2") (pin "3") (pinfunction "PWRKEY_3") (pintype "passive"))
    )
    (net (code "55") (name "Net-(Q5-BASE)") (class "Default")
      (node (ref "Q5") (pin "1") (pinfunction "BASE_1") (pintype "passive"))
      (node (ref "R17") (pin "2") (pinfunction "2_2") (pintype "passive"))
      (node (ref "R18") (pin "1") (pinfunction "1_1") (pintype "passive"))
    )
    (net (code "56") (name "Net-(Q5-COLLECTOR)") (class "Default")
      (node (ref "Q5") (pin "3") (pinfunction "COLLECTOR_3") (pintype "passive"))
      (node (ref "U2") (pin "4") (pinfunction "RESET_4") (pintype "passive"))
    )
    (net (code "57") (name "Net-(U1-ADJ)") (class "Default")
      (node (ref "R5") (pin "1") (pinfunction "1_1") (pintype "passive"))
      (node (ref "R7") (pin "1") (pinfunction "1_1") (pintype "passive"))
      (node (ref "U1") (pin "5") (pinfunction "ADJ_5") (pintype "passive"))
    )
    (net (code "58") (name "Net-(U2-USIM_CLK)") (class "Default")
      (node (ref "R16") (pin "2") (pinfunction "2_2") (pintype "passive"))
      (node (ref "U2") (pin "19") (pinfunction "USIM_CLK_19") (pintype "passive"))
    )
    (net (code "59") (name "Net-(U3-A1)") (class "Default")
      (node (ref "R20") (pin "1") (pinfunction "1_1") (pintype "passive"))
      (node (ref "U3") (pin "1") (pinfunction "A1_1") (pintype "passive"))
      (node (ref "U3") (pin "3") (pinfunction "A2_3") (pintype "passive"))
      (node (ref "U3") (pin "4") (pinfunction "A3_4") (pintype "passive"))
    )
    (net (code "60") (name "Net-(U3-B1)") (class "Default")
      (node (ref "R21") (pin "2") (pinfunction "2_2") (pintype "passive"))
      (node (ref "U3") (pin "17") (pinfunction "B3_17") (pintype "passive"))
      (node (ref "U3") (pin "18") (pinfunction "B2_18") (pintype "passive"))
      (node (ref "U3") (pin "20") (pinfunction "B1_20") (pintype "passive"))
    )
    (net (code "61") (name "Net-(U3-B4)") (class "Default")
      (node (ref "R27") (pin "2") (pinfunction "2_2") (pintype "passive"))
      (node (ref "U3") (pin "16") (pinfunction "B4_16") (pintype "passive"))
    )
    (net (code "62") (name "Net-(U3-B5)") (class "Default")
      (node (ref "R28") (pin "2") (pinfunction "2_2") (pintype "passive"))
      (node (ref "U3") (pin "15") (pinfunction "B5_15") (pintype "passive"))
    )
    (net (code "63") (name "VDD1V8") (class "Default")
      (node (ref "C17") (pin "2") (pinfunction "2_2") (pintype "passive"))
      (node (ref "R23") (pin "1") (pinfunction "1_1") (pintype "passive"))
      (node (ref "R24") (pin "1") (pinfunction "1_1") (pintype "passive"))
      (node (ref "R25") (pin "1") (pinfunction "1_1") (pintype "passive"))
      (node (ref "R26") (pin "1") (pinfunction "1_1") (pintype "passive"))
      (node (ref "R29") (pin "2") (pinfunction "2_2") (pintype "passive"))
      (node (ref "R30") (pin "2") (pinfunction "2_2") (pintype "passive"))
      (node (ref "U2") (pin "15") (pinfunction "VDD_1V8_15") (pintype "passive"))
      (node (ref "U3") (pin "10") (pinfunction "OE_10") (pintype "passive"))
      (node (ref "U3") (pin "2") (pinfunction "VCCA_2") (pintype "passive"))
    )
    (net (code "64") (name "unconnected-(J1-VPP-Pad6)") (class "Default")
      (node (ref "J1") (pin "6") (pinfunction "VPP_6") (pintype "passive"))
    )
    (net (code "65") (name "unconnected-(U2-ADC1-Pad47)") (class "Default")
      (node (ref "U2") (pin "47") (pinfunction "ADC1_47") (pintype "passive"))
    )
    (net (code "66") (name "unconnected-(U2-ADC2-Pad46)") (class "Default")
      (node (ref "U2") (pin "46") (pinfunction "ADC2_46") (pintype "passive"))
    )
    (net (code "67") (name "unconnected-(U2-AUX_ANT-Pad59)") (class "Default")
      (node (ref "U2") (pin "59") (pinfunction "AUX_ANT_59") (pintype "passive"))
    )
    (net (code "68") (name "unconnected-(U2-COEX3-Pad86)") (class "Default")
      (node (ref "U2") (pin "86") (pinfunction "COEX3_86") (pintype "passive"))
    )
    (net (code "69") (name "unconnected-(U2-ISINK-Pad45)") (class "Default")
      (node (ref "U2") (pin "45") (pinfunction "ISINK_45") (pintype "passive"))
    )
    (net (code "70") (name "unconnected-(U2-KBC0-Pad28)") (class "Default")
      (node (ref "U2") (pin "28") (pinfunction "KBC0_28") (pintype "passive"))
    )
    (net (code "71") (name "unconnected-(U2-KBC1-Pad27)") (class "Default")
      (node (ref "U2") (pin "27") (pinfunction "KBC1_27") (pintype "passive"))
    )
    (net (code "72") (name "unconnected-(U2-KBC2-Pad31)") (class "Default")
      (node (ref "U2") (pin "31") (pinfunction "KBC2_31") (pintype "passive"))
    )
    (net (code "73") (name "unconnected-(U2-KBC3-Pad32)") (class "Default")
      (node (ref "U2") (pin "32") (pinfunction "KBC3_32") (pintype "passive"))
    )
    (net (code "74") (name "unconnected-(U2-KBC4-Pad36)") (class "Default")
      (node (ref "U2") (pin "36") (pinfunction "KBC4_36") (pintype "passive"))
    )
    (net (code "75") (name "unconnected-(U2-KBR0-Pad29)") (class "Default")
      (node (ref "U2") (pin "29") (pinfunction "KBR0_29") (pintype "passive"))
    )
    (net (code "76") (name "unconnected-(U2-KBR1-Pad33)") (class "Default")
      (node (ref "U2") (pin "33") (pinfunction "KBR1_33") (pintype "passive"))
    )
    (net (code "77") (name "unconnected-(U2-KBR2-Pad30)") (class "Default")
      (node (ref "U2") (pin "30") (pinfunction "KBR2_30") (pintype "passive"))
    )
    (net (code "78") (name "unconnected-(U2-KBR3-Pad35)") (class "Default")
      (node (ref "U2") (pin "35") (pinfunction "KBR3_35") (pintype "passive"))
    )
    (net (code "79") (name "unconnected-(U2-KBR4-Pad34)") (class "Default")
      (node (ref "U2") (pin "34") (pinfunction "KBR4_34") (pintype "passive"))
    )
    (net (code "80") (name "unconnected-(U2-NC-Pad42)") (class "Default")
      (node (ref "U2") (pin "42") (pinfunction "NC_42") (pintype "passive"))
    )
    (net (code "81") (name "unconnected-(U2-PCM_CLK-Pad76)") (class "Default")
      (node (ref "U2") (pin "76") (pinfunction "PCM_CLK_76") (pintype "passive"))
    )
    (net (code "82") (name "unconnected-(U2-PCM_IN-Pad74)") (class "Default")
      (node (ref "U2") (pin "74") (pinfunction "PCM_IN_74") (pintype "passive"))
    )
    (net (code "83") (name "unconnected-(U2-PCM_OUT-Pad73)") (class "Default")
      (node (ref "U2") (pin "73") (pinfunction "PCM_OUT_73") (pintype "passive"))
    )
    (net (code "84") (name "unconnected-(U2-PCM_SYNC-Pad75)") (class "Default")
      (node (ref "U2") (pin "75") (pinfunction "PCM_SYNC_75") (pintype "passive"))
    )
    (net (code "85") (name "unconnected-(U2-SCL-Pad55)") (class "Default")
      (node (ref "U2") (pin "55") (pinfunction "SCL_55") (pintype "passive"))
    )
    (net (code "86") (name "unconnected-(U2-SD1_DET-Pad48)") (class "Default")
      (node (ref "U2") (pin "48") (pinfunction "SD1_DET_48") (pintype "passive"))
    )
    (net (code "87") (name "unconnected-(U2-SDA-Pad56)") (class "Default")
      (node (ref "U2") (pin "56") (pinfunction "SDA_56") (pintype "passive"))
    )
    (net (code "88") (name "unconnected-(U2-SD_CLK-Pad26)") (class "Default")
      (node (ref "U2") (pin "26") (pinfunction "SD_CLK_26") (pintype "passive"))
    )
    (net (code "89") (name "unconnected-(U2-SD_CMD-Pad21)") (class "Default")
      (node (ref "U2") (pin "21") (pinfunction "SD_CMD_21") (pintype "passive"))
    )
    (net (code "90") (name "unconnected-(U2-SD_DATA0-Pad22)") (class "Default")
      (node (ref "U2") (pin "22") (pinfunction "SD_DATA0_22") (pintype "passive"))
    )
    (net (code "91") (name "unconnected-(U2-SD_DATA1-Pad23)") (class "Default")
      (node (ref "U2") (pin "23") (pinfunction "SD_DATA1_23") (pintype "passive"))
    )
    (net (code "92") (name "unconnected-(U2-SD_DATA2-Pad24)") (class "Default")
      (node (ref "U2") (pin "24") (pinfunction "SD_DATA2_24") (pintype "passive"))
    )
    (net (code "93") (name "unconnected-(U2-SD_DATA3-Pad25)") (class "Default")
      (node (ref "U2") (pin "25") (pinfunction "SD_DATA3_25") (pintype "passive"))
    )
    (net (code "94") (name "unconnected-(U2-SPI_CLK-Pad6)") (class "Default")
      (node (ref "U2") (pin "6") (pinfunction "SPI_CLK_6") (pintype "passive"))
    )
    (net (code "95") (name "unconnected-(U2-SPI_CS-Pad9)") (class "Default")
      (node (ref "U2") (pin "9") (pinfunction "SPI_CS_9") (pintype "passive"))
    )
    (net (code "96") (name "unconnected-(U2-SPI_MISO-Pad7)") (class "Default")
      (node (ref "U2") (pin "7") (pinfunction "SPI_MISO_7") (pintype "passive"))
    )
    (net (code "97") (name "unconnected-(U2-SPI_MOSI-Pad8)") (class "Default")
      (node (ref "U2") (pin "8") (pinfunction "SPI_MOSI_8") (pintype "passive"))
    )
    (net (code "98") (name "unconnected-(U2-USIM_DET-Pad53)") (class "Default")
      (node (ref "U2") (pin "53") (pinfunction "USIM_DET_53") (pintype "passive"))
    )
    (net (code "99") (name "unconnected-(U2-VDD_EXT-Pad44)") (class "Default")
      (node (ref "U2") (pin "44") (pinfunction "VDD_EXT_44") (pintype "passive"))
    )
  )
)
